# FuE_Schaltplan18.net
KiCad netlist of a schematic drawn in EAGLE
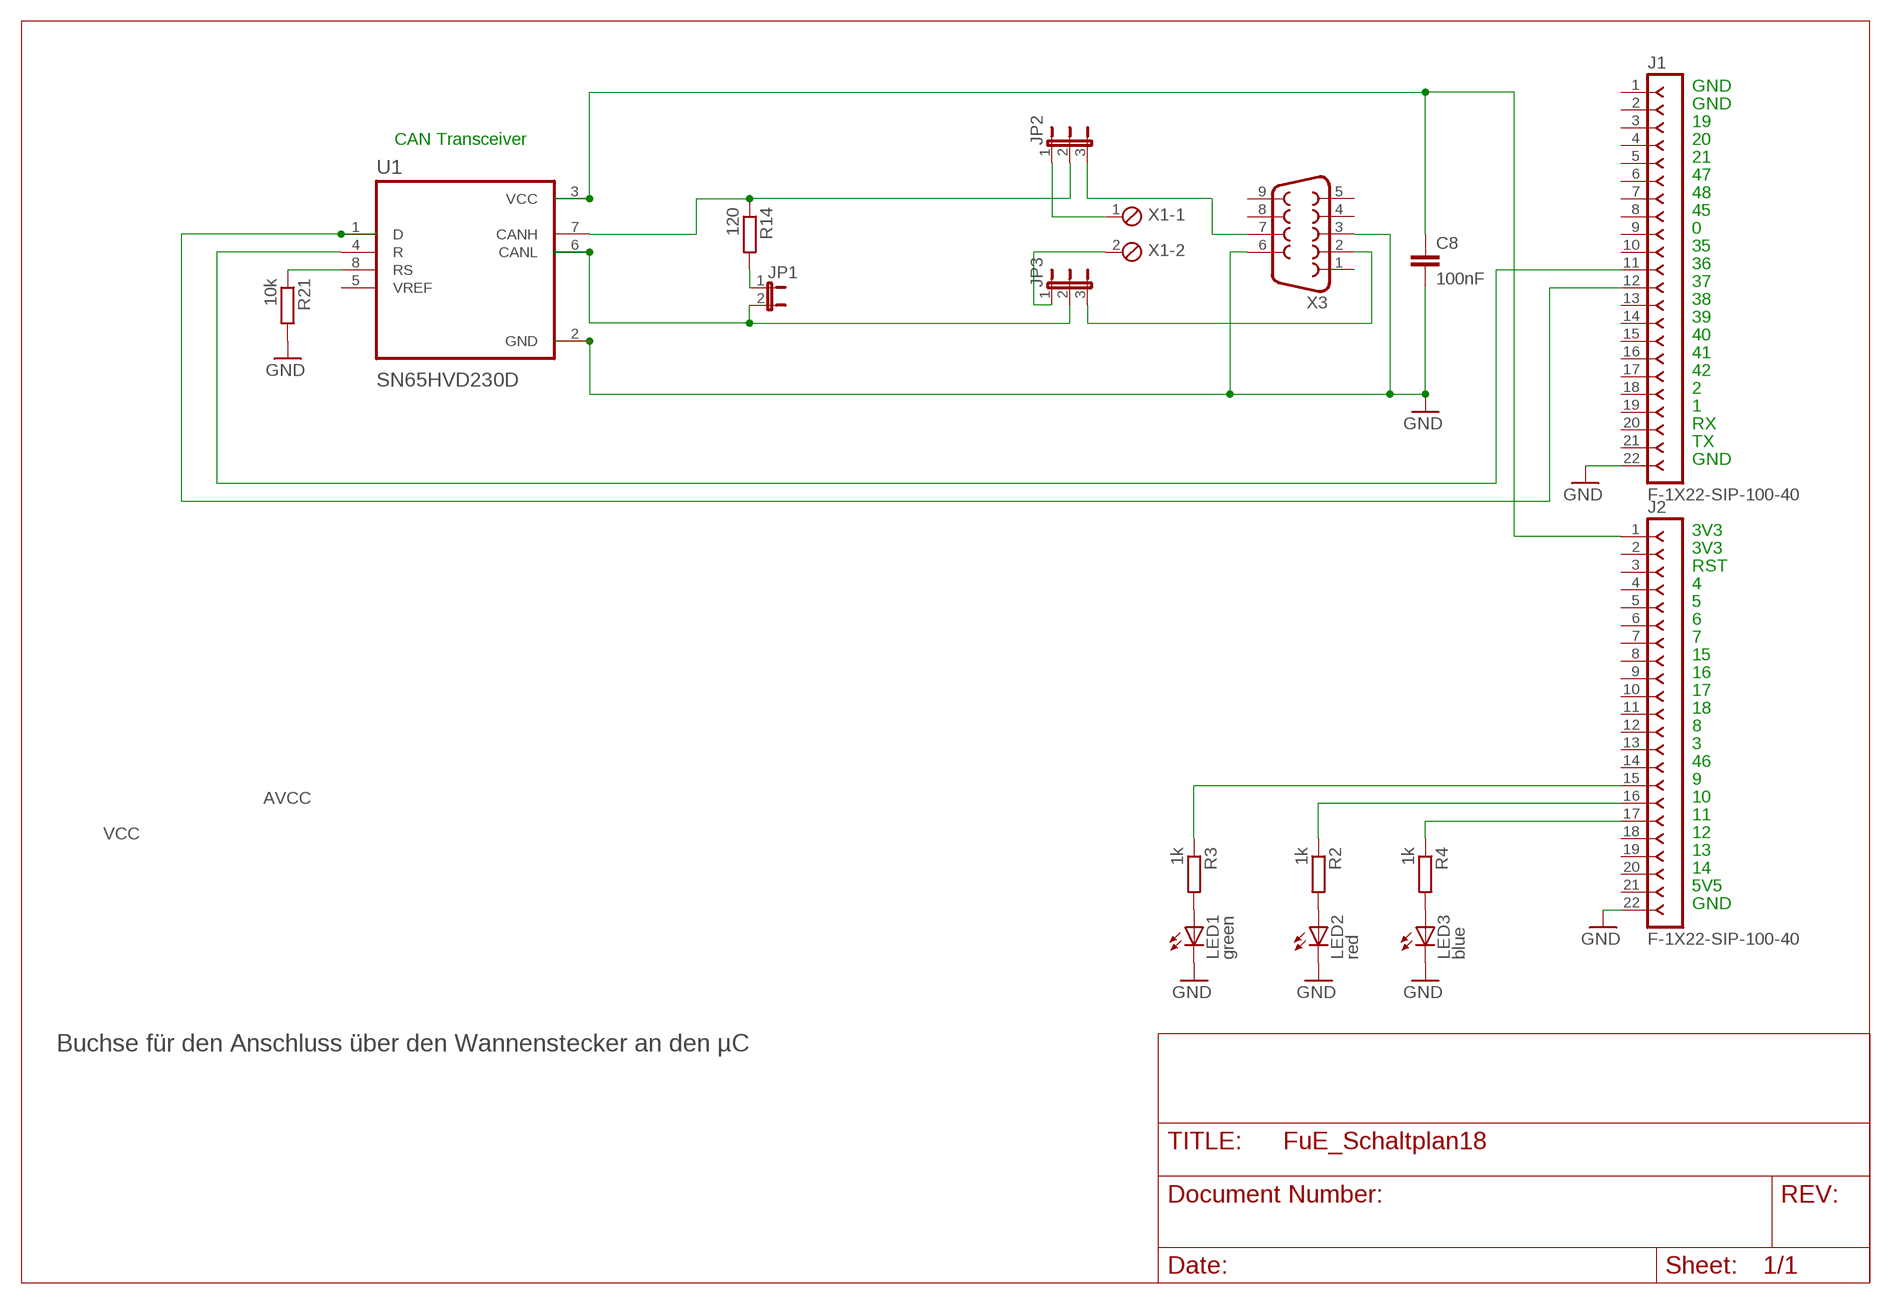
[diagram p0: schematic, sheet 1]

(export (version "E")
  (design (tool "Eeschema 10.0.6"))
  (components
    (comp (ref "C8")
      (value "100nF")
      (footprint "eagle-import:C0805")
      (libsource (lib "eagle-import") (part "C-EUC0805"))
    )
    (comp (ref "J1")
      (value "F-1X22-SIP-100-40")
      (footprint "eagle-import:SIP-100-22-40")
      (libsource (lib "eagle-import") (part "F-1X22-SIP-100-40"))
    )
    (comp (ref "J2")
      (value "F-1X22-SIP-100-40")
      (footprint "eagle-import:SIP-100-22-40")
      (libsource (lib "eagle-import") (part "F-1X22-SIP-100-40"))
    )
    (comp (ref "JP1")
      (value "JP1E")
      (footprint "eagle-import:JP1")
      (libsource (lib "eagle-import") (part "JP1E"))
    )
    (comp (ref "JP2")
      (value "JP2E")
      (footprint "eagle-import:JP2")
      (libsource (lib "eagle-import") (part "JP2E"))
    )
    (comp (ref "JP3")
      (value "JP2E")
      (footprint "eagle-import:JP2")
      (libsource (lib "eagle-import") (part "JP2E"))
    )
    (comp (ref "LED1")
      (value "green")
      (footprint "eagle-import:CHIP-LED0805")
      (libsource (lib "eagle-import") (part "LEDCHIP-LED0805"))
    )
    (comp (ref "LED2")
      (value "red")
      (footprint "eagle-import:CHIP-LED0805")
      (libsource (lib "eagle-import") (part "LEDCHIP-LED0805"))
    )
    (comp (ref "LED3")
      (value "blue")
      (footprint "eagle-import:CHIP-LED0805")
      (libsource (lib "eagle-import") (part "LEDCHIP-LED0805"))
    )
    (comp (ref "R2")
      (value "1k")
      (footprint "eagle-import:R0805")
      (libsource (lib "eagle-import") (part "R-EU_R0805"))
    )
    (comp (ref "R3")
      (value "1k")
      (footprint "eagle-import:R0805")
      (libsource (lib "eagle-import") (part "R-EU_R0805"))
    )
    (comp (ref "R4")
      (value "1k")
      (footprint "eagle-import:R0805")
      (libsource (lib "eagle-import") (part "R-EU_R0805"))
    )
    (comp (ref "R14")
      (value "120")
      (footprint "eagle-import:R0805")
      (libsource (lib "eagle-import") (part "R-EU_R0805"))
    )
    (comp (ref "R21")
      (value "10k")
      (footprint "eagle-import:R0805")
      (libsource (lib "eagle-import") (part "R-EU_R0805"))
    )
    (comp (ref "U1")
      (value "SN65HVD230D")
      (footprint "eagle-import:SOIC127P599X175-8N")
      (fields (field (name "MF") "Texas Instruments"))
      (libsource (lib "eagle-import") (part "SN65HVD230D"))
    )
    (comp (ref "X1")
      (value "MPT2")
      (footprint "eagle-import:2POL254")
      (libsource (lib "eagle-import") (part "MPT2"))
    )
    (comp (ref "X3")
      (value "F09VP")
      (footprint "eagle-import:F09VP")
      (libsource (lib "eagle-import") (part "F09VP"))
    )
  )
  (nets
    (net (code "1") (name "GND") (class "Default")
      (node (ref "C8") (pin "2") (pinfunction "2_2") (pintype "passive"))
      (node (ref "J1") (pin "22") (pinfunction "22_22") (pintype "passive"))
      (node (ref "J2") (pin "22") (pinfunction "22_22") (pintype "passive"))
      (node (ref "LED1") (pin "C") (pinfunction "C_C") (pintype "passive"))
      (node (ref "LED2") (pin "C") (pinfunction "C_C") (pintype "passive"))
      (node (ref "LED3") (pin "C") (pinfunction "C_C") (pintype "passive"))
      (node (ref "R21") (pin "2") (pinfunction "2_2") (pintype "passive"))
      (node (ref "U1") (pin "2") (pinfunction "GND_2") (pintype "power_in"))
      (node (ref "X3") (pin "3") (pinfunction "3_3") (pintype "passive"))
      (node (ref "X3") (pin "6") (pinfunction "6_6") (pintype "passive"))
    )
    (net (code "2") (name "Net-(J2-Pad15)") (class "Default")
      (node (ref "J2") (pin "15") (pinfunction "15_15") (pintype "passive"))
      (node (ref "R3") (pin "1") (pinfunction "1_1") (pintype "passive"))
    )
    (net (code "3") (name "Net-(J2-Pad16)") (class "Default")
      (node (ref "J2") (pin "16") (pinfunction "16_16") (pintype "passive"))
      (node (ref "R2") (pin "1") (pinfunction "1_1") (pintype "passive"))
    )
    (net (code "4") (name "Net-(J2-Pad17)") (class "Default")
      (node (ref "J2") (pin "17") (pinfunction "17_17") (pintype "passive"))
      (node (ref "R4") (pin "1") (pinfunction "1_1") (pintype "passive"))
    )
    (net (code "5") (name "Net-(JP1-Pad1)") (class "Default")
      (node (ref "JP1") (pin "1") (pinfunction "1_1") (pintype "passive"))
      (node (ref "R14") (pin "2") (pinfunction "2_2") (pintype "passive"))
    )
    (net (code "6") (name "Net-(JP2-Pad1)") (class "Default")
      (node (ref "JP2") (pin "1") (pinfunction "1_1") (pintype "passive"))
      (node (ref "X1") (pin "1") (pinfunction "1_1") (pintype "passive"))
    )
    (net (code "7") (name "Net-(JP2-Pad3)") (class "Default")
      (node (ref "JP2") (pin "3") (pinfunction "3_3") (pintype "passive"))
      (node (ref "X3") (pin "7") (pinfunction "7_7") (pintype "passive"))
    )
    (net (code "8") (name "Net-(JP3-Pad3)") (class "Default")
      (node (ref "JP3") (pin "3") (pinfunction "3_3") (pintype "passive"))
      (node (ref "X3") (pin "2") (pinfunction "2_2") (pintype "passive"))
    )
    (net (code "9") (name "Net-(LED1-PadA)") (class "Default")
      (node (ref "LED1") (pin "A") (pinfunction "A_A") (pintype "passive"))
      (node (ref "R3") (pin "2") (pinfunction "2_2") (pintype "passive"))
    )
    (net (code "10") (name "Net-(LED2-PadA)") (class "Default")
      (node (ref "LED2") (pin "A") (pinfunction "A_A") (pintype "passive"))
      (node (ref "R2") (pin "2") (pinfunction "2_2") (pintype "passive"))
    )
    (net (code "11") (name "Net-(LED3-PadA)") (class "Default")
      (node (ref "LED3") (pin "A") (pinfunction "A_A") (pintype "passive"))
      (node (ref "R4") (pin "2") (pinfunction "2_2") (pintype "passive"))
    )
    (net (code "12") (name "Net-(U1-CANH)") (class "Default")
      (node (ref "JP2") (pin "2") (pinfunction "2_2") (pintype "passive"))
      (node (ref "R14") (pin "1") (pinfunction "1_1") (pintype "passive"))
      (node (ref "U1") (pin "7") (pinfunction "CANH_7") (pintype "output"))
    )
    (net (code "13") (name "Net-(U1-CANL)") (class "Default")
      (node (ref "JP1") (pin "2") (pinfunction "2_2") (pintype "passive"))
      (node (ref "JP3") (pin "2") (pinfunction "2_2") (pintype "passive"))
      (node (ref "U1") (pin "6") (pinfunction "CANL_6") (pintype "output"))
    )
    (net (code "14") (name "Net-(U1-D)") (class "Default")
      (node (ref "J1") (pin "12") (pinfunction "12_12") (pintype "passive"))
      (node (ref "U1") (pin "1") (pinfunction "D_1") (pintype "input"))
    )
    (net (code "15") (name "Net-(U1-R)") (class "Default")
      (node (ref "J1") (pin "11") (pinfunction "11_11") (pintype "passive"))
      (node (ref "U1") (pin "4") (pinfunction "R_4") (pintype "input"))
    )
    (net (code "16") (name "Net-(U1-RS)") (class "Default")
      (node (ref "R21") (pin "1") (pinfunction "1_1") (pintype "passive"))
      (node (ref "U1") (pin "8") (pinfunction "RS_8") (pintype "input"))
    )
    (net (code "17") (name "Net-(U1-VCC)") (class "Default")
      (node (ref "C8") (pin "1") (pinfunction "1_1") (pintype "passive"))
      (node (ref "J2") (pin "1") (pinfunction "1_1") (pintype "passive"))
      (node (ref "U1") (pin "3") (pinfunction "VCC_3") (pintype "power_in"))
    )
    (net (code "18") (name "Net-(X1B-1)") (class "Default")
      (node (ref "JP3") (pin "1") (pinfunction "1_1") (pintype "passive"))
      (node (ref "X1") (pin "2") (pinfunction "1_2") (pintype "passive"))
    )
    (net (code "19") (name "unconnected-(J1-Pad1)") (class "Default")
      (node (ref "J1") (pin "1") (pinfunction "1_1") (pintype "passive"))
    )
    (net (code "20") (name "unconnected-(J1-Pad2)") (class "Default")
      (node (ref "J1") (pin "2") (pinfunction "2_2") (pintype "passive"))
    )
    (net (code "21") (name "unconnected-(J1-Pad3)") (class "Default")
      (node (ref "J1") (pin "3") (pinfunction "3_3") (pintype "passive"))
    )
    (net (code "22") (name "unconnected-(J1-Pad4)") (class "Default")
      (node (ref "J1") (pin "4") (pinfunction "4_4") (pintype "passive"))
    )
    (net (code "23") (name "unconnected-(J1-Pad5)") (class "Default")
      (node (ref "J1") (pin "5") (pinfunction "5_5") (pintype "passive"))
    )
    (net (code "24") (name "unconnected-(J1-Pad6)") (class "Default")
      (node (ref "J1") (pin "6") (pinfunction "6_6") (pintype "passive"))
    )
    (net (code "25") (name "unconnected-(J1-Pad7)") (class "Default")
      (node (ref "J1") (pin "7") (pinfunction "7_7") (pintype "passive"))
    )
    (net (code "26") (name "unconnected-(J1-Pad8)") (class "Default")
      (node (ref "J1") (pin "8") (pinfunction "8_8") (pintype "passive"))
    )
    (net (code "27") (name "unconnected-(J1-Pad9)") (class "Default")
      (node (ref "J1") (pin "9") (pinfunction "9_9") (pintype "passive"))
    )
    (net (code "28") (name "unconnected-(J1-Pad10)") (class "Default")
      (node (ref "J1") (pin "10") (pinfunction "10_10") (pintype "passive"))
    )
    (net (code "29") (name "unconnected-(J1-Pad13)") (class "Default")
      (node (ref "J1") (pin "13") (pinfunction "13_13") (pintype "passive"))
    )
    (net (code "30") (name "unconnected-(J1-Pad14)") (class "Default")
      (node (ref "J1") (pin "14") (pinfunction "14_14") (pintype "passive"))
    )
    (net (code "31") (name "unconnected-(J1-Pad15)") (class "Default")
      (node (ref "J1") (pin "15") (pinfunction "15_15") (pintype "passive"))
    )
    (net (code "32") (name "unconnected-(J1-Pad16)") (class "Default")
      (node (ref "J1") (pin "16") (pinfunction "16_16") (pintype "passive"))
    )
    (net (code "33") (name "unconnected-(J1-Pad17)") (class "Default")
      (node (ref "J1") (pin "17") (pinfunction "17_17") (pintype "passive"))
    )
    (net (code "34") (name "unconnected-(J1-Pad18)") (class "Default")
      (node (ref "J1") (pin "18") (pinfunction "18_18") (pintype "passive"))
    )
    (net (code "35") (name "unconnected-(J1-Pad19)") (class "Default")
      (node (ref "J1") (pin "19") (pinfunction "19_19") (pintype "passive"))
    )
    (net (code "36") (name "unconnected-(J1-Pad20)") (class "Default")
      (node (ref "J1") (pin "20") (pinfunction "20_20") (pintype "passive"))
    )
    (net (code "37") (name "unconnected-(J1-Pad21)") (class "Default")
      (node (ref "J1") (pin "21") (pinfunction "21_21") (pintype "passive"))
    )
    (net (code "38") (name "unconnected-(J2-Pad2)") (class "Default")
      (node (ref "J2") (pin "2") (pinfunction "2_2") (pintype "passive"))
    )
    (net (code "39") (name "unconnected-(J2-Pad3)") (class "Default")
      (node (ref "J2") (pin "3") (pinfunction "3_3") (pintype "passive"))
    )
    (net (code "40") (name "unconnected-(J2-Pad4)") (class "Default")
      (node (ref "J2") (pin "4") (pinfunction "4_4") (pintype "passive"))
    )
    (net (code "41") (name "unconnected-(J2-Pad5)") (class "Default")
      (node (ref "J2") (pin "5") (pinfunction "5_5") (pintype "passive"))
    )
    (net (code "42") (name "unconnected-(J2-Pad6)") (class "Default")
      (node (ref "J2") (pin "6") (pinfunction "6_6") (pintype "passive"))
    )
    (net (code "43") (name "unconnected-(J2-Pad7)") (class "Default")
      (node (ref "J2") (pin "7") (pinfunction "7_7") (pintype "passive"))
    )
    (net (code "44") (name "unconnected-(J2-Pad8)") (class "Default")
      (node (ref "J2") (pin "8") (pinfunction "8_8") (pintype "passive"))
    )
    (net (code "45") (name "unconnected-(J2-Pad9)") (class "Default")
      (node (ref "J2") (pin "9") (pinfunction "9_9") (pintype "passive"))
    )
    (net (code "46") (name "unconnected-(J2-Pad10)") (class "Default")
      (node (ref "J2") (pin "10") (pinfunction "10_10") (pintype "passive"))
    )
    (net (code "47") (name "unconnected-(J2-Pad11)") (class "Default")
      (node (ref "J2") (pin "11") (pinfunction "11_11") (pintype "passive"))
    )
    (net (code "48") (name "unconnected-(J2-Pad12)") (class "Default")
      (node (ref "J2") (pin "12") (pinfunction "12_12") (pintype "passive"))
    )
    (net (code "49") (name "unconnected-(J2-Pad13)") (class "Default")
      (node (ref "J2") (pin "13") (pinfunction "13_13") (pintype "passive"))
    )
    (net (code "50") (name "unconnected-(J2-Pad14)") (class "Default")
      (node (ref "J2") (pin "14") (pinfunction "14_14") (pintype "passive"))
    )
    (net (code "51") (name "unconnected-(J2-Pad18)") (class "Default")
      (node (ref "J2") (pin "18") (pinfunction "18_18") (pintype "passive"))
    )
    (net (code "52") (name "unconnected-(J2-Pad19)") (class "Default")
      (node (ref "J2") (pin "19") (pinfunction "19_19") (pintype "passive"))
    )
    (net (code "53") (name "unconnected-(J2-Pad20)") (class "Default")
      (node (ref "J2") (pin "20") (pinfunction "20_20") (pintype "passive"))
    )
    (net (code "54") (name "unconnected-(J2-Pad21)") (class "Default")
      (node (ref "J2") (pin "21") (pinfunction "21_21") (pintype "passive"))
    )
    (net (code "55") (name "unconnected-(U1-VREF-Pad5)") (class "Default")
      (node (ref "U1") (pin "5") (pinfunction "VREF_5") (pintype "input"))
    )
    (net (code "56") (name "unconnected-(X3-Pad1)") (class "Default")
      (node (ref "X3") (pin "1") (pinfunction "1_1") (pintype "passive"))
    )
    (net (code "57") (name "unconnected-(X3-Pad4)") (class "Default")
      (node (ref "X3") (pin "4") (pinfunction "4_4") (pintype "passive"))
    )
    (net (code "58") (name "unconnected-(X3-Pad5)") (class "Default")
      (node (ref "X3") (pin "5") (pinfunction "5_5") (pintype "passive"))
    )
    (net (code "59") (name "unconnected-(X3-Pad8)") (class "Default")
      (node (ref "X3") (pin "8") (pinfunction "8_8") (pintype "passive"))
    )
    (net (code "60") (name "unconnected-(X3-Pad9)") (class "Default")
      (node (ref "X3") (pin "9") (pinfunction "9_9") (pintype "passive"))
    )
  )
)
